# Depth_Sensor_for_SPL1301_V1_0.net
KiCad netlist of a schematic drawn in Altium Designer
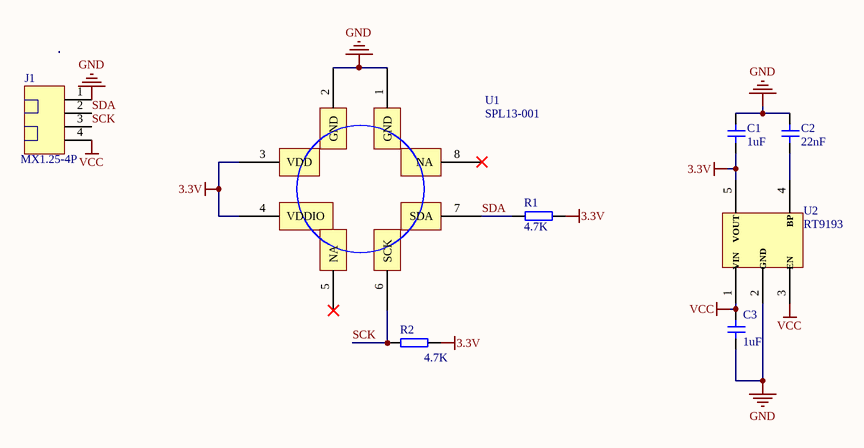
[diagram p0: Depth Sensor for SPL1301 V1.0.SchDoc]

(export (version "E")
  (design (tool "Eeschema 10.0.6"))
  (components
    (comp (ref "C1")
      (value "1uF")
      (footprint "0603C")
      (description "无极贴片电容")
      (libsource (lib "My ku") (part "Cap1"))
    )
    (comp (ref "C2")
      (value "22nF")
      (footprint "0603C")
      (description "无极贴片电容")
      (libsource (lib "My ku") (part "Cap1"))
    )
    (comp (ref "C3")
      (value "1uF")
      (footprint "0603C")
      (description "无极贴片电容")
      (libsource (lib "My ku") (part "Cap1"))
    )
    (comp (ref "J1")
      (value "MX1.25-4P")
      (footprint "MX1.25-4P")
      (libsource (lib "Schlib1") (part "MX1.25-4P_1"))
    )
    (comp (ref "R1")
      (value "4.7K")
      (footprint "0603R")
      (description "电阻")
      (libsource (lib "My ku") (part "Res"))
    )
    (comp (ref "R2")
      (value "4.7K")
      (footprint "0603R")
      (description "电阻")
      (libsource (lib "My ku") (part "Res"))
    )
    (comp (ref "U1")
      (value "SPL13-001")
      (footprint "SPL13-001")
      (libsource (lib "Schlib1") (part "SPL13-001_1"))
    )
    (comp (ref "U2") (value "RT9193") (footprint "RT9193") (libsource (lib "Schlib1") (part "RT9193")))
  )
  (nets
    (net (code "1") (name "/SCK") (class "Default")
      (node (ref "J1") (pin "3") (pinfunction "3_3") (pintype "passive"))
      (node (ref "R2") (pin "2") (pinfunction "2_2") (pintype "passive"))
      (node (ref "U1") (pin "6") (pinfunction "SCK_6") (pintype "passive"))
    )
    (net (code "2") (name "/SDA") (class "Default")
      (node (ref "J1") (pin "2") (pinfunction "2_2") (pintype "passive"))
      (node (ref "R1") (pin "2") (pinfunction "2_2") (pintype "passive"))
      (node (ref "U1") (pin "7") (pinfunction "SDA_7") (pintype "passive"))
    )
    (net (code "3") (name "3.3V") (class "Default")
      (node (ref "C1") (pin "1") (pinfunction "1_1") (pintype "passive"))
      (node (ref "R1") (pin "1") (pinfunction "1_1") (pintype "passive"))
      (node (ref "R2") (pin "1") (pinfunction "1_1") (pintype "passive"))
      (node (ref "U1") (pin "3") (pinfunction "VDD_3") (pintype "passive"))
      (node (ref "U1") (pin "4") (pinfunction "VDDIO_4") (pintype "passive"))
      (node (ref "U2") (pin "5") (pinfunction "VOUT_5") (pintype "passive"))
    )
    (net (code "4") (name "GND") (class "Default")
      (node (ref "C1") (pin "2") (pinfunction "2_2") (pintype "passive"))
      (node (ref "C2") (pin "2") (pinfunction "2_2") (pintype "passive"))
      (node (ref "C3") (pin "1") (pinfunction "1_1") (pintype "passive"))
      (node (ref "J1") (pin "1") (pinfunction "1_1") (pintype "passive"))
      (node (ref "U1") (pin "1") (pinfunction "GND_1") (pintype "passive"))
      (node (ref "U1") (pin "2") (pinfunction "GND_2") (pintype "passive"))
      (node (ref "U2") (pin "2") (pinfunction "GND_2") (pintype "passive"))
    )
    (net (code "5") (name "Net-(U2-BP)") (class "Default")
      (node (ref "C2") (pin "1") (pinfunction "1_1") (pintype "passive"))
      (node (ref "U2") (pin "4") (pinfunction "BP_4") (pintype "passive"))
    )
    (net (code "6") (name "VCC") (class "Default")
      (node (ref "C3") (pin "2") (pinfunction "2_2") (pintype "passive"))
      (node (ref "J1") (pin "4") (pinfunction "4_4") (pintype "passive"))
      (node (ref "U2") (pin "1") (pinfunction "VIN_1") (pintype "passive"))
      (node (ref "U2") (pin "3") (pinfunction "EN_3") (pintype "passive"))
    )
    (net (code "7") (name "unconnected-(U1-NA-Pad5)") (class "Default")
      (node (ref "U1") (pin "5") (pinfunction "NA_5") (pintype "passive+no_connect"))
    )
    (net (code "8") (name "unconnected-(U1-NA-Pad8)") (class "Default")
      (node (ref "U1") (pin "8") (pinfunction "NA_8") (pintype "passive+no_connect"))
    )
  )
)
